# mosfet.net
KiCad netlist of a schematic drawn in Altium Designer
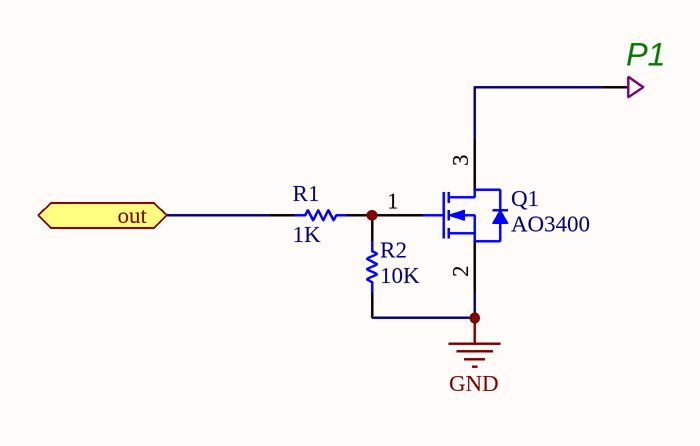
[diagram p0: mosfet.SchDoc]

(export (version "E")
  (design (tool "Eeschema 10.0.6"))
  (components
    (comp (ref "P1") (value "pin") (footprint "pin") (libsource (lib "moya") (part "pin")))
    (comp (ref "Q1")
      (value "AO3400")
      (footprint "AO-SOT23-3_V")
      (description "N-channel Enhancement Mode Field-Effect Transistor; 5.8A/30V")
      (fields (field (name "MANUFACTURER") "Alpha and Omega"))
      (libsource (lib "Altium Content Vault") (part "AO-NEMOS-G1S2D3-3"))
    )
    (comp (ref "R1")
      (value "1K")
      (footprint "RESC2013X70X40ML20T20")
      (description "RES SMD 150K OHM 1% 1/8W 0805")
      (fields (field (name "MANUFACTURER") "Panasonic") (field (name "PART NUMBER") "ERJ-6ENF1503V"))
      (libsource (lib "Altium Content Vault") (part "CMP-2001-04440-2"))
    )
    (comp (ref "R2")
      (value "10K")
      (footprint "RESC2013X70X40ML20T20")
      (description "RES SMD 150K OHM 1% 1/8W 0805")
      (fields (field (name "MANUFACTURER") "Panasonic") (field (name "PART NUMBER") "ERJ-6ENF1503V"))
      (libsource (lib "Altium Content Vault") (part "CMP-2001-04440-2"))
    )
  )
  (nets
    (net (code "1") (name "/out") (class "Default")
      (node (ref "R1") (pin "2") (pinfunction "2_2") (pintype "passive"))
    )
    (net (code "2") (name "GND") (class "Default")
      (node (ref "Q1") (pin "2") (pinfunction "S_2") (pintype "passive"))
      (node (ref "R2") (pin "2") (pinfunction "2_2") (pintype "passive"))
    )
    (net (code "3") (name "Net-(Q1-D)") (class "Default")
      (node (ref "P1") (pin "0") (pinfunction "0_0") (pintype "passive"))
      (node (ref "Q1") (pin "3") (pinfunction "D_3") (pintype "passive"))
    )
    (net (code "4") (name "Net-(Q1-G)") (class "Default")
      (node (ref "Q1") (pin "1") (pinfunction "G_1") (pintype "passive"))
      (node (ref "R1") (pin "1") (pinfunction "1_1") (pintype "passive"))
      (node (ref "R2") (pin "1") (pinfunction "1_1") (pintype "passive"))
    )
  )
)
